# devils-rectangle.net
KiCad netlist of a schematic drawn in EAGLE
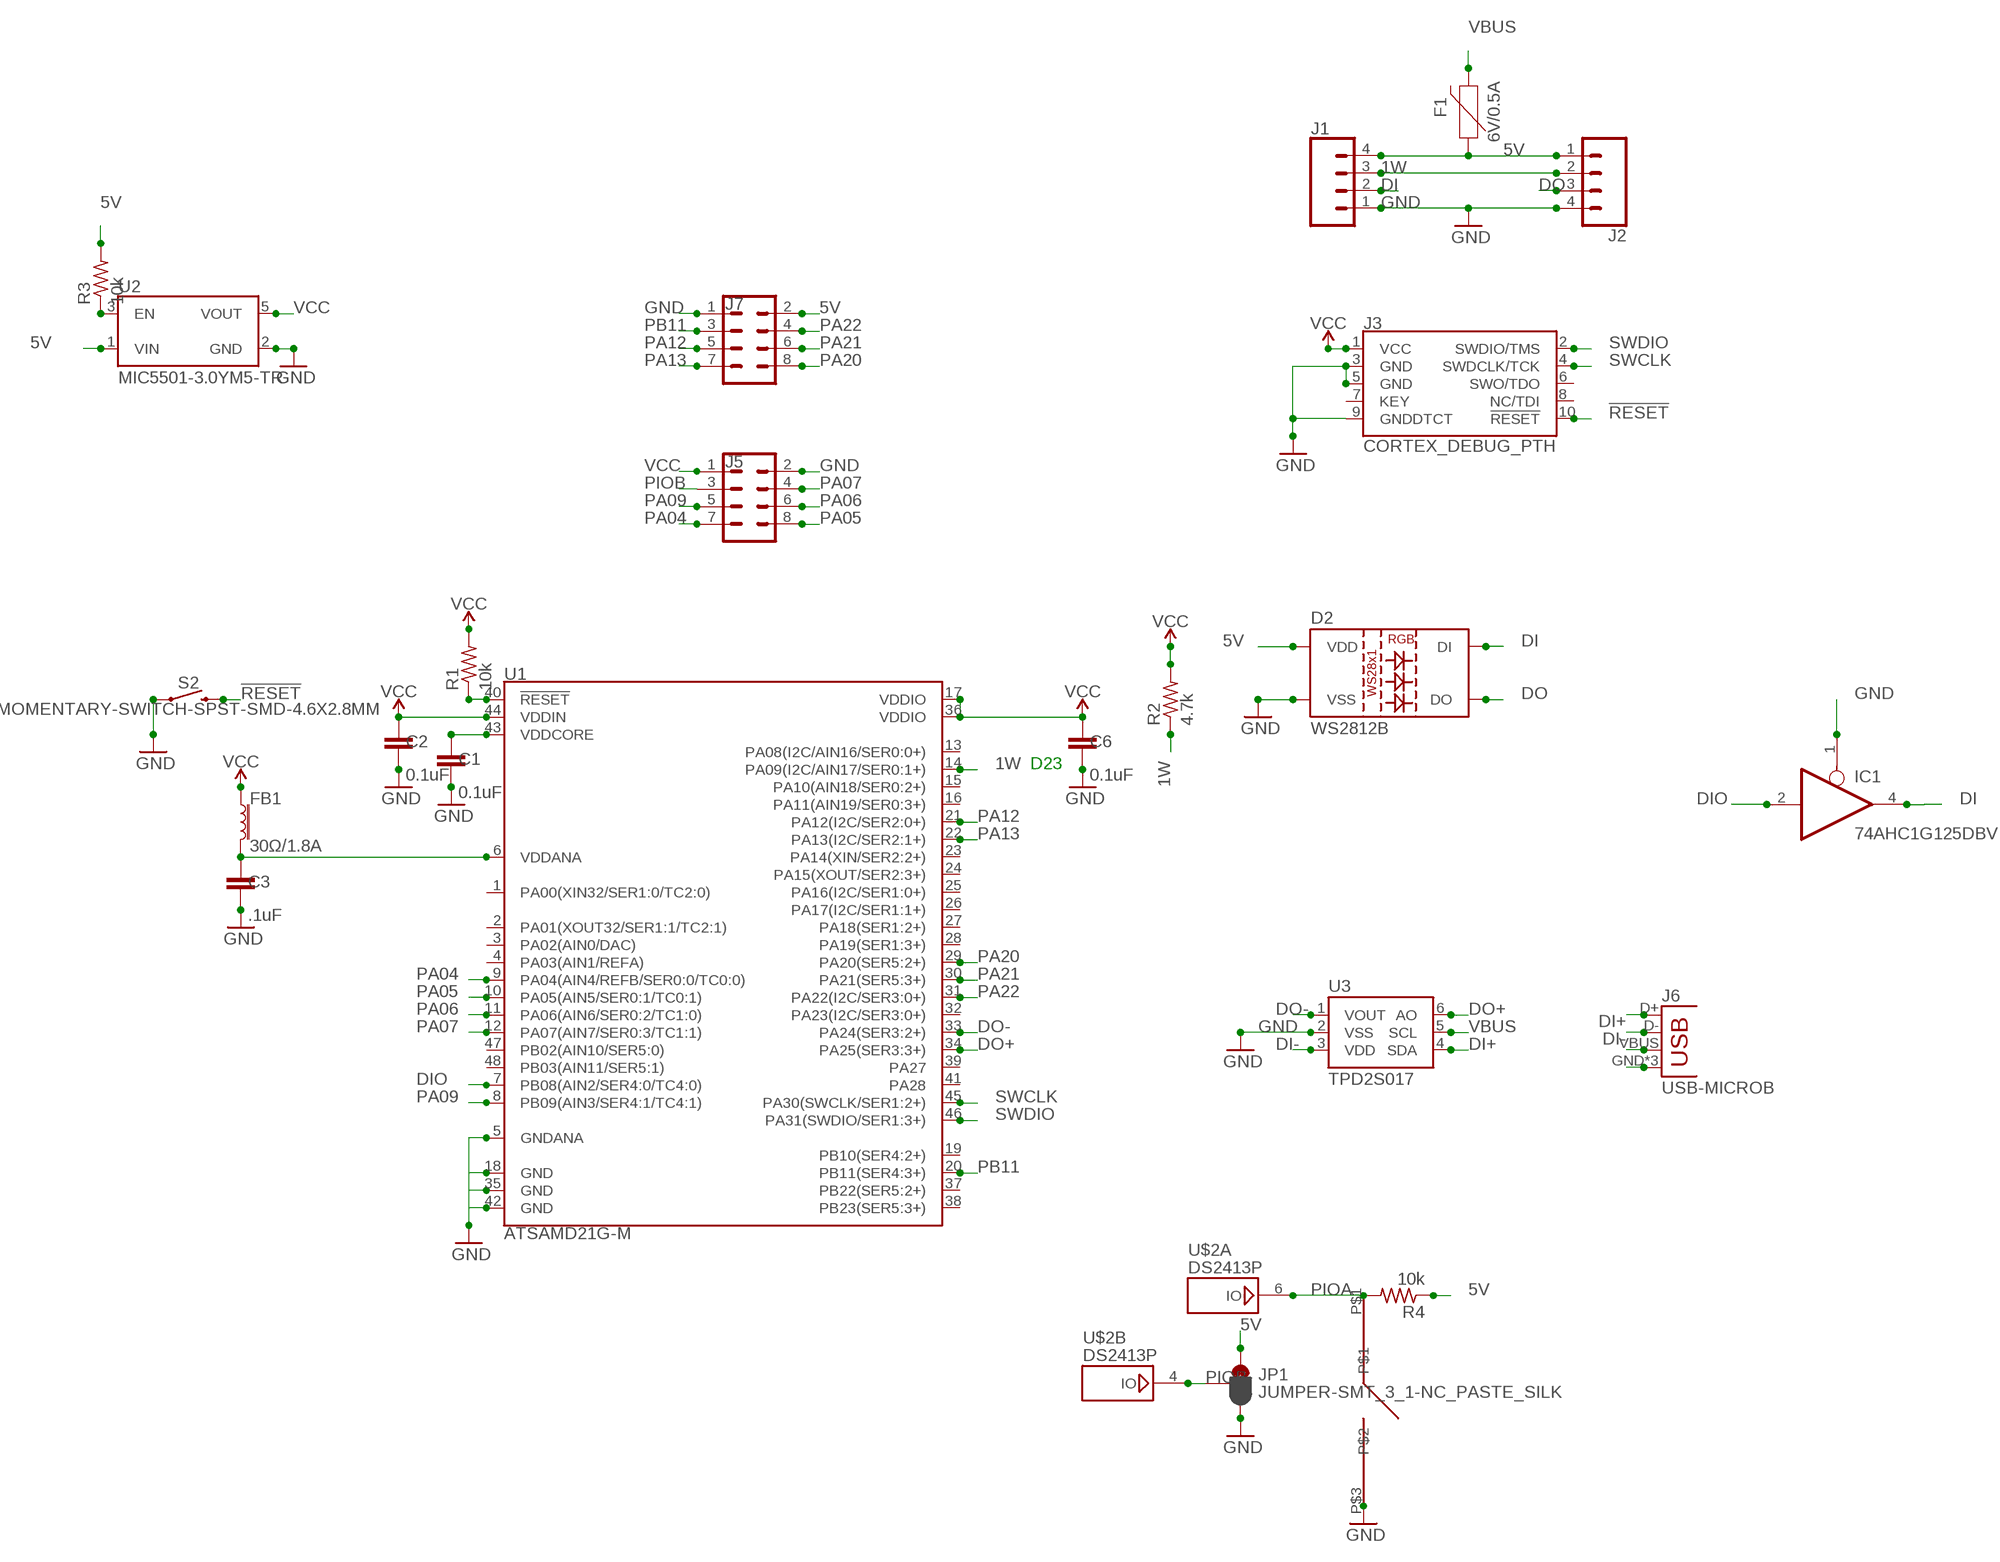
[diagram p0: schematic, sheet 1]

(export (version "E")
  (design (tool "Eeschema 10.0.6"))
  (components
    (comp (ref "C1")
      (value "0.1uF")
      (footprint "eagle-import:0402")
      (libsource (lib "eagle-import") (part "0.1UF-0402-16V-10%"))
    )
    (comp (ref "C2")
      (value "0.1uF")
      (footprint "eagle-import:0402")
      (libsource (lib "eagle-import") (part "0.1UF-0402-16V-10%"))
    )
    (comp (ref "C3")
      (value ".1uF")
      (footprint "eagle-import:0402")
      (libsource (lib "eagle-import") (part "0.1UF-0402-16V-10%"))
    )
    (comp (ref "C6")
      (value "0.1uF")
      (footprint "eagle-import:0402")
      (libsource (lib "eagle-import") (part "0.1UF-0402-16V-10%"))
    )
    (comp (ref "D2")
      (value "WS2812B")
      (footprint "eagle-import:WS2812B")
      (libsource (lib "eagle-import") (part "WS2812B"))
    )
    (comp (ref "F1")
      (value "6V/0.5A")
      (footprint "eagle-import:1206")
      (libsource (lib "eagle-import") (part "PPTC_HALF-AMP"))
    )
    (comp (ref "FB1")
      (value "30Ω/1.8A")
      (footprint "eagle-import:0603")
      (libsource (lib "eagle-import") (part "FERRITE_BEAD-0603"))
    )
    (comp (ref "IC1")
      (value "74AHC1G125DBV")
      (footprint "eagle-import:SOT23-5")
      (libsource (lib "eagle-import") (part "741G125DBVAHC"))
    )
    (comp (ref "J1")
      (value "CONN_04SMD2")
      (footprint "eagle-import:1X04_1MM_RA")
      (libsource (lib "eagle-import") (part "CONN_04SMD2"))
    )
    (comp (ref "J2")
      (value "CONN_04SMD2")
      (footprint "eagle-import:1X04_1MM_RA")
      (libsource (lib "eagle-import") (part "CONN_04SMD2"))
    )
    (comp (ref "J3")
      (value "CORTEX_DEBUG_PTH")
      (footprint "eagle-import:2X5-PTH-1.27MM")
      (libsource (lib "eagle-import") (part "CORTEX_DEBUG_PTH"))
    )
    (comp (ref "J5")
      (value "CONN_04X2")
      (footprint "eagle-import:2X4")
      (libsource (lib "eagle-import") (part "CONN_04X2"))
    )
    (comp (ref "J6")
      (value "USB-MICROB")
      (footprint "eagle-import:USB-MICROB")
      (libsource (lib "eagle-import") (part "USB-MICROB"))
    )
    (comp (ref "J7")
      (value "CONN_04X2")
      (footprint "eagle-import:2X4")
      (libsource (lib "eagle-import") (part "CONN_04X2"))
    )
    (comp (ref "JP1")
      (value "JUMPER-SMT_3_1-NC_PASTE_SILK")
      (footprint "eagle-import:SMT-JUMPER_3_1-NC_PASTE_SILK")
      (libsource (lib "eagle-import") (part "JUMPER-SMT_3_1-NC_PASTE_SILK"))
    )
    (comp (ref "R1")
      (value "10k")
      (footprint "eagle-import:R0402")
      (libsource (lib "eagle-import") (part "R-US_R0402"))
    )
    (comp (ref "R2")
      (value "4.7k")
      (footprint "eagle-import:R0402")
      (libsource (lib "eagle-import") (part "R-US_R0402"))
    )
    (comp (ref "R3")
      (value "10k")
      (footprint "eagle-import:R0402")
      (libsource (lib "eagle-import") (part "R-US_R0402"))
    )
    (comp (ref "R4")
      (value "10k")
      (footprint "eagle-import:R0402")
      (libsource (lib "eagle-import") (part "R-US_R0402"))
    )
    (comp (ref "S2")
      (value "MOMENTARY-SWITCH-SPST-SMD-4.6X2.8MM")
      (footprint "eagle-import:TACTILE_SWITCH_SMD_4.6X2.8MM")
      (libsource (lib "eagle-import") (part "MOMENTARY-SWITCH-SPST-SMD-4.6X2.8MM"))
    )
    (comp (ref "U$1")
      (value "NOVELKEY")
      (footprint "eagle-import:NOVELKEY")
      (libsource (lib "eagle-import") (part "NOVELKEY"))
    )
    (comp (ref "U$2")
      (value "DS2413P")
      (footprint "eagle-import:TSOC6")
      (libsource (lib "eagle-import") (part "DS2413P"))
    )
    (comp (ref "U1")
      (value "ATSAMD21G-M")
      (footprint "eagle-import:QFN-48")
      (libsource (lib "eagle-import") (part "ATSAMD21G-M"))
    )
    (comp (ref "U2")
      (value "MIC5501-3.0YM5-TR")
      (footprint "eagle-import:SOT95P280X145-5N")
      (fields (field (name "MF") "Microchip"))
      (libsource (lib "eagle-import") (part "MIC5501-3.0YM5-TR"))
    )
    (comp (ref "U3")
      (value "TPD2S017")
      (footprint "eagle-import:SOT23-6")
      (libsource (lib "eagle-import") (part "MCP4725SOT-23"))
    )
  )
  (nets
    (net (code "1") (name "/1W") (class "Default")
      (node (ref "J1") (pin "3") (pinfunction "3_3") (pintype "passive"))
      (node (ref "J2") (pin "2") (pinfunction "2_2") (pintype "passive"))
      (node (ref "R2") (pin "1") (pinfunction "1_1") (pintype "passive"))
      (node (ref "U1") (pin "14") (pinfunction "PA09(I2C/AIN17/SER0:1+)_14") (pintype "bidirectional"))
    )
    (net (code "2") (name "/5V") (class "Default")
      (node (ref "D2") (pin "1") (pinfunction "VDD_1") (pintype "bidirectional"))
      (node (ref "F1") (pin "1") (pinfunction "1_1") (pintype "bidirectional"))
      (node (ref "J1") (pin "4") (pinfunction "4_4") (pintype "passive"))
      (node (ref "J2") (pin "1") (pinfunction "1_1") (pintype "passive"))
      (node (ref "J7") (pin "2") (pinfunction "2_2") (pintype "passive"))
      (node (ref "JP1") (pin "1") (pinfunction "1_1") (pintype "passive"))
      (node (ref "R3") (pin "2") (pinfunction "2_2") (pintype "passive"))
      (node (ref "R4") (pin "1") (pinfunction "1_1") (pintype "passive"))
      (node (ref "U2") (pin "1") (pinfunction "VIN_1") (pintype "input"))
    )
    (net (code "3") (name "/DI") (class "Default")
      (node (ref "D2") (pin "4") (pinfunction "DI_4") (pintype "bidirectional"))
      (node (ref "IC1") (pin "4") (pinfunction "O_4") (pintype "tri_state"))
      (node (ref "J1") (pin "2") (pinfunction "2_2") (pintype "passive"))
    )
    (net (code "4") (name "/DI+") (class "Default")
      (node (ref "J6") (pin "D+") (pinfunction "D+_D+") (pintype "bidirectional"))
      (node (ref "U3") (pin "4") (pinfunction "SDA_4") (pintype "bidirectional"))
    )
    (net (code "5") (name "/DI-") (class "Default")
      (node (ref "J6") (pin "D-") (pinfunction "D-_D-") (pintype "bidirectional"))
      (node (ref "U3") (pin "3") (pinfunction "VDD_3") (pintype "bidirectional"))
    )
    (net (code "6") (name "/DIO") (class "Default")
      (node (ref "IC1") (pin "2") (pinfunction "I_2") (pintype "input"))
      (node (ref "U1") (pin "7") (pinfunction "PB08(AIN2/SER4:0/TC4:0)_7") (pintype "bidirectional"))
    )
    (net (code "7") (name "/DO") (class "Default")
      (node (ref "D2") (pin "2") (pinfunction "DO_2") (pintype "bidirectional"))
      (node (ref "J2") (pin "3") (pinfunction "3_3") (pintype "passive"))
    )
    (net (code "8") (name "/DO+") (class "Default")
      (node (ref "U1") (pin "34") (pinfunction "PA25(SER3:3+)_34") (pintype "bidirectional"))
      (node (ref "U3") (pin "6") (pinfunction "AO_6") (pintype "bidirectional"))
    )
    (net (code "9") (name "/DO-") (class "Default")
      (node (ref "U1") (pin "33") (pinfunction "PA24(SER3:2+)_33") (pintype "bidirectional"))
      (node (ref "U3") (pin "1") (pinfunction "VOUT_1") (pintype "bidirectional"))
    )
    (net (code "10") (name "/PA04") (class "Default")
      (node (ref "J5") (pin "7") (pinfunction "7_7") (pintype "passive"))
      (node (ref "U1") (pin "9") (pinfunction "PA04(AIN4/REFB/SER0:0/TC0:0)_9") (pintype "bidirectional"))
    )
    (net (code "11") (name "/PA05") (class "Default")
      (node (ref "J5") (pin "8") (pinfunction "8_8") (pintype "passive"))
      (node (ref "U1") (pin "10") (pinfunction "PA05(AIN5/SER0:1/TC0:1)_10") (pintype "bidirectional"))
    )
    (net (code "12") (name "/PA06") (class "Default")
      (node (ref "J5") (pin "6") (pinfunction "6_6") (pintype "passive"))
      (node (ref "U1") (pin "11") (pinfunction "PA06(AIN6/SER0:2/TC1:0)_11") (pintype "bidirectional"))
    )
    (net (code "13") (name "/PA07") (class "Default")
      (node (ref "J5") (pin "4") (pinfunction "4_4") (pintype "passive"))
      (node (ref "U1") (pin "12") (pinfunction "PA07(AIN7/SER0:3/TC1:1)_12") (pintype "bidirectional"))
    )
    (net (code "14") (name "/PA09") (class "Default")
      (node (ref "J5") (pin "5") (pinfunction "5_5") (pintype "passive"))
      (node (ref "U1") (pin "8") (pinfunction "PB09(AIN3/SER4:1/TC4:1)_8") (pintype "bidirectional"))
    )
    (net (code "15") (name "/PA12") (class "Default")
      (node (ref "J7") (pin "5") (pinfunction "5_5") (pintype "passive"))
      (node (ref "U1") (pin "21") (pinfunction "PA12(I2C/SER2:0+)_21") (pintype "bidirectional"))
    )
    (net (code "16") (name "/PA13") (class "Default")
      (node (ref "J7") (pin "7") (pinfunction "7_7") (pintype "passive"))
      (node (ref "U1") (pin "22") (pinfunction "PA13(I2C/SER2:1+)_22") (pintype "bidirectional"))
    )
    (net (code "17") (name "/PA20") (class "Default")
      (node (ref "J7") (pin "8") (pinfunction "8_8") (pintype "passive"))
      (node (ref "U1") (pin "29") (pinfunction "PA20(SER5:2+)_29") (pintype "bidirectional"))
    )
    (net (code "18") (name "/PA21") (class "Default")
      (node (ref "J7") (pin "6") (pinfunction "6_6") (pintype "passive"))
      (node (ref "U1") (pin "30") (pinfunction "PA21(SER5:3+)_30") (pintype "bidirectional"))
    )
    (net (code "19") (name "/PA22") (class "Default")
      (node (ref "J7") (pin "4") (pinfunction "4_4") (pintype "passive"))
      (node (ref "U1") (pin "31") (pinfunction "PA22(I2C/SER3:0+)_31") (pintype "bidirectional"))
    )
    (net (code "20") (name "/PB11") (class "Default")
      (node (ref "J7") (pin "3") (pinfunction "3_3") (pintype "passive"))
      (node (ref "U1") (pin "20") (pinfunction "PB11(SER4:3+)_20") (pintype "bidirectional"))
    )
    (net (code "21") (name "/PIOA") (class "Default")
      (node (ref "R4") (pin "2") (pinfunction "2_2") (pintype "passive"))
      (node (ref "U$1") (pin "P$1") (pinfunction "P$1_P$1") (pintype "bidirectional"))
      (node (ref "U$2") (pin "6") (pinfunction "IO_6") (pintype "open_collector"))
    )
    (net (code "22") (name "/PIOB") (class "Default")
      (node (ref "J5") (pin "3") (pinfunction "3_3") (pintype "passive"))
      (node (ref "JP1") (pin "2") (pinfunction "2_2") (pintype "passive"))
      (node (ref "U$2") (pin "4") (pinfunction "IO_4") (pintype "open_collector"))
    )
    (net (code "23") (name "/SWCLK") (class "Default")
      (node (ref "J3") (pin "4") (pinfunction "SWDCLK/TCK_4") (pintype "bidirectional"))
      (node (ref "U1") (pin "45") (pinfunction "PA30(SWCLK/SER1:2+)_45") (pintype "bidirectional"))
    )
    (net (code "24") (name "/SWDIO") (class "Default")
      (node (ref "J3") (pin "2") (pinfunction "SWDIO/TMS_2") (pintype "bidirectional"))
      (node (ref "U1") (pin "46") (pinfunction "PA31(SWDIO/SER1:3+)_46") (pintype "bidirectional"))
    )
    (net (code "25") (name "/VBUS") (class "Default")
      (node (ref "F1") (pin "2") (pinfunction "2_2") (pintype "bidirectional"))
      (node (ref "J6") (pin "VBUS") (pinfunction "VBUS_VBUS") (pintype "bidirectional"))
      (node (ref "U3") (pin "5") (pinfunction "SCL_5") (pintype "bidirectional"))
    )
    (net (code "26") (name "/~{RESET}") (class "Default")
      (node (ref "J3") (pin "10") (pinfunction "~{RESET}_10") (pintype "bidirectional"))
      (node (ref "R1") (pin "1") (pinfunction "1_1") (pintype "passive"))
      (node (ref "S2") (pin "3") (pinfunction "2_3") (pintype "passive"))
      (node (ref "S2") (pin "4") (pinfunction "2_4") (pintype "passive"))
      (node (ref "U1") (pin "40") (pinfunction "~{RESET}_40") (pintype "bidirectional"))
    )
    (net (code "27") (name "GND") (class "Default")
      (node (ref "C1") (pin "2") (pinfunction "2_2") (pintype "passive"))
      (node (ref "C2") (pin "2") (pinfunction "2_2") (pintype "passive"))
      (node (ref "C3") (pin "2") (pinfunction "2_2") (pintype "passive"))
      (node (ref "C6") (pin "2") (pinfunction "2_2") (pintype "passive"))
      (node (ref "D2") (pin "3") (pinfunction "VSS_3") (pintype "bidirectional"))
      (node (ref "IC1") (pin "1") (pinfunction "OE_1") (pintype "input"))
      (node (ref "J1") (pin "1") (pinfunction "1_1") (pintype "passive"))
      (node (ref "J2") (pin "4") (pinfunction "4_4") (pintype "passive"))
      (node (ref "J3") (pin "3") (pinfunction "GND_3") (pintype "bidirectional"))
      (node (ref "J3") (pin "5") (pinfunction "GND_5") (pintype "bidirectional"))
      (node (ref "J3") (pin "9") (pinfunction "GNDDTCT_9") (pintype "bidirectional"))
      (node (ref "J5") (pin "2") (pinfunction "2_2") (pintype "passive"))
      (node (ref "J6") (pin "GND") (pinfunction "GND_GND") (pintype "bidirectional"))
      (node (ref "J6") (pin "MT1") (pinfunction "GND_MT1") (pintype "bidirectional"))
      (node (ref "J6") (pin "MT2") (pinfunction "GND_MT2") (pintype "bidirectional"))
      (node (ref "J7") (pin "1") (pinfunction "1_1") (pintype "passive"))
      (node (ref "JP1") (pin "3") (pinfunction "3_3") (pintype "passive"))
      (node (ref "S2") (pin "1") (pinfunction "1_1") (pintype "passive"))
      (node (ref "S2") (pin "2") (pinfunction "1_2") (pintype "passive"))
      (node (ref "U$1") (pin "P$3") (pinfunction "P$2_P$3") (pintype "bidirectional"))
      (node (ref "U1") (pin "18") (pinfunction "GND_18") (pintype "bidirectional"))
      (node (ref "U1") (pin "35") (pinfunction "GND_35") (pintype "bidirectional"))
      (node (ref "U1") (pin "42") (pinfunction "GND_42") (pintype "bidirectional"))
      (node (ref "U1") (pin "5") (pinfunction "GNDANA_5") (pintype "bidirectional"))
      (node (ref "U2") (pin "2") (pinfunction "GND_2") (pintype "power_in"))
      (node (ref "U3") (pin "2") (pinfunction "VSS_2") (pintype "bidirectional"))
    )
    (net (code "28") (name "Net-(U1-VDDANA)") (class "Default")
      (node (ref "C3") (pin "1") (pinfunction "1_1") (pintype "passive"))
      (node (ref "FB1") (pin "2") (pinfunction "2_2") (pintype "passive"))
      (node (ref "U1") (pin "6") (pinfunction "VDDANA_6") (pintype "bidirectional"))
    )
    (net (code "29") (name "Net-(U1-VDDCORE)") (class "Default")
      (node (ref "C1") (pin "1") (pinfunction "1_1") (pintype "passive"))
      (node (ref "U1") (pin "43") (pinfunction "VDDCORE_43") (pintype "bidirectional"))
    )
    (net (code "30") (name "Net-(U2-EN)") (class "Default")
      (node (ref "R3") (pin "1") (pinfunction "1_1") (pintype "passive"))
      (node (ref "U2") (pin "3") (pinfunction "EN_3") (pintype "input"))
    )
    (net (code "31") (name "VCC") (class "Default")
      (node (ref "C2") (pin "1") (pinfunction "1_1") (pintype "passive"))
      (node (ref "C6") (pin "1") (pinfunction "1_1") (pintype "passive"))
      (node (ref "FB1") (pin "1") (pinfunction "1_1") (pintype "passive"))
      (node (ref "J3") (pin "1") (pinfunction "VCC_1") (pintype "bidirectional"))
      (node (ref "J5") (pin "1") (pinfunction "1_1") (pintype "passive"))
      (node (ref "R1") (pin "2") (pinfunction "2_2") (pintype "passive"))
      (node (ref "R2") (pin "2") (pinfunction "2_2") (pintype "passive"))
      (node (ref "U1") (pin "17") (pinfunction "VDDIO_17") (pintype "bidirectional"))
      (node (ref "U1") (pin "36") (pinfunction "VDDIO_36") (pintype "bidirectional"))
      (node (ref "U1") (pin "44") (pinfunction "VDDIN_44") (pintype "bidirectional"))
      (node (ref "U2") (pin "5") (pinfunction "VOUT_5") (pintype "output"))
    )
    (net (code "32") (name "unconnected-(J3-KEY-Pad7)") (class "Default")
      (node (ref "J3") (pin "7") (pinfunction "KEY_7") (pintype "bidirectional"))
    )
    (net (code "33") (name "unconnected-(J3-NC{slash}TDI-Pad8)") (class "Default")
      (node (ref "J3") (pin "8") (pinfunction "NC/TDI_8") (pintype "bidirectional"))
    )
    (net (code "34") (name "unconnected-(J3-SWO{slash}TDO-Pad6)") (class "Default")
      (node (ref "J3") (pin "6") (pinfunction "SWO/TDO_6") (pintype "bidirectional"))
    )
    (net (code "35") (name "unconnected-(U1-PA00(XIN32{slash}SER1:0{slash}TC2:0)-Pad1)") (class "Default")
      (node (ref "U1") (pin "1") (pinfunction "PA00(XIN32/SER1:0/TC2:0)_1") (pintype "bidirectional"))
    )
    (net (code "36") (name "unconnected-(U1-PA01(XOUT32{slash}SER1:1{slash}TC2:1)-Pad2)") (class "Default")
      (node (ref "U1") (pin "2") (pinfunction "PA01(XOUT32/SER1:1/TC2:1)_2") (pintype "bidirectional"))
    )
    (net (code "37") (name "unconnected-(U1-PA02(AIN0{slash}DAC)-Pad3)") (class "Default")
      (node (ref "U1") (pin "3") (pinfunction "PA02(AIN0/DAC)_3") (pintype "bidirectional"))
    )
    (net (code "38") (name "unconnected-(U1-PA03(AIN1{slash}REFA)-Pad4)") (class "Default")
      (node (ref "U1") (pin "4") (pinfunction "PA03(AIN1/REFA)_4") (pintype "bidirectional"))
    )
    (net (code "39") (name "unconnected-(U1-PA08(I2C{slash}AIN16{slash}SER0:0+)-Pad13)") (class "Default")
      (node (ref "U1") (pin "13") (pinfunction "PA08(I2C/AIN16/SER0:0+)_13") (pintype "bidirectional"))
    )
    (net (code "40") (name "unconnected-(U1-PA10(AIN18{slash}SER0:2+)-Pad15)") (class "Default")
      (node (ref "U1") (pin "15") (pinfunction "PA10(AIN18/SER0:2+)_15") (pintype "bidirectional"))
    )
    (net (code "41") (name "unconnected-(U1-PA11(AIN19{slash}SER0:3+)-Pad16)") (class "Default")
      (node (ref "U1") (pin "16") (pinfunction "PA11(AIN19/SER0:3+)_16") (pintype "bidirectional"))
    )
    (net (code "42") (name "unconnected-(U1-PA14(XIN{slash}SER2:2+)-Pad23)") (class "Default")
      (node (ref "U1") (pin "23") (pinfunction "PA14(XIN/SER2:2+)_23") (pintype "bidirectional"))
    )
    (net (code "43") (name "unconnected-(U1-PA15(XOUT{slash}SER2:3+)-Pad24)") (class "Default")
      (node (ref "U1") (pin "24") (pinfunction "PA15(XOUT/SER2:3+)_24") (pintype "bidirectional"))
    )
    (net (code "44") (name "unconnected-(U1-PA16(I2C{slash}SER1:0+)-Pad25)") (class "Default")
      (node (ref "U1") (pin "25") (pinfunction "PA16(I2C/SER1:0+)_25") (pintype "bidirectional"))
    )
    (net (code "45") (name "unconnected-(U1-PA17(I2C{slash}SER1:1+)-Pad26)") (class "Default")
      (node (ref "U1") (pin "26") (pinfunction "PA17(I2C/SER1:1+)_26") (pintype "bidirectional"))
    )
    (net (code "46") (name "unconnected-(U1-PA18(SER1:2+)-Pad27)") (class "Default")
      (node (ref "U1") (pin "27") (pinfunction "PA18(SER1:2+)_27") (pintype "bidirectional"))
    )
    (net (code "47") (name "unconnected-(U1-PA19(SER1:3+)-Pad28)") (class "Default")
      (node (ref "U1") (pin "28") (pinfunction "PA19(SER1:3+)_28") (pintype "bidirectional"))
    )
    (net (code "48") (name "unconnected-(U1-PA23(I2C{slash}SER3:0+)-Pad32)") (class "Default")
      (node (ref "U1") (pin "32") (pinfunction "PA23(I2C/SER3:0+)_32") (pintype "bidirectional"))
    )
    (net (code "49") (name "unconnected-(U1-PA27-Pad39)") (class "Default")
      (node (ref "U1") (pin "39") (pinfunction "PA27_39") (pintype "bidirectional"))
    )
    (net (code "50") (name "unconnected-(U1-PA28-Pad41)") (class "Default")
      (node (ref "U1") (pin "41") (pinfunction "PA28_41") (pintype "bidirectional"))
    )
    (net (code "51") (name "unconnected-(U1-PB02(AIN10{slash}SER5:0)-Pad47)") (class "Default")
      (node (ref "U1") (pin "47") (pinfunction "PB02(AIN10/SER5:0)_47") (pintype "bidirectional"))
    )
    (net (code "52") (name "unconnected-(U1-PB03(AIN11{slash}SER5:1)-Pad48)") (class "Default")
      (node (ref "U1") (pin "48") (pinfunction "PB03(AIN11/SER5:1)_48") (pintype "bidirectional"))
    )
    (net (code "53") (name "unconnected-(U1-PB10(SER4:2+)-Pad19)") (class "Default")
      (node (ref "U1") (pin "19") (pinfunction "PB10(SER4:2+)_19") (pintype "bidirectional"))
    )
    (net (code "54") (name "unconnected-(U1-PB22(SER5:2+)-Pad37)") (class "Default")
      (node (ref "U1") (pin "37") (pinfunction "PB22(SER5:2+)_37") (pintype "bidirectional"))
    )
    (net (code "55") (name "unconnected-(U1-PB23(SER5:3+)-Pad38)") (class "Default")
      (node (ref "U1") (pin "38") (pinfunction "PB23(SER5:3+)_38") (pintype "bidirectional"))
    )
  )
)
